# xnemo_r1-1.net
KiCad netlist of a schematic drawn in EAGLE
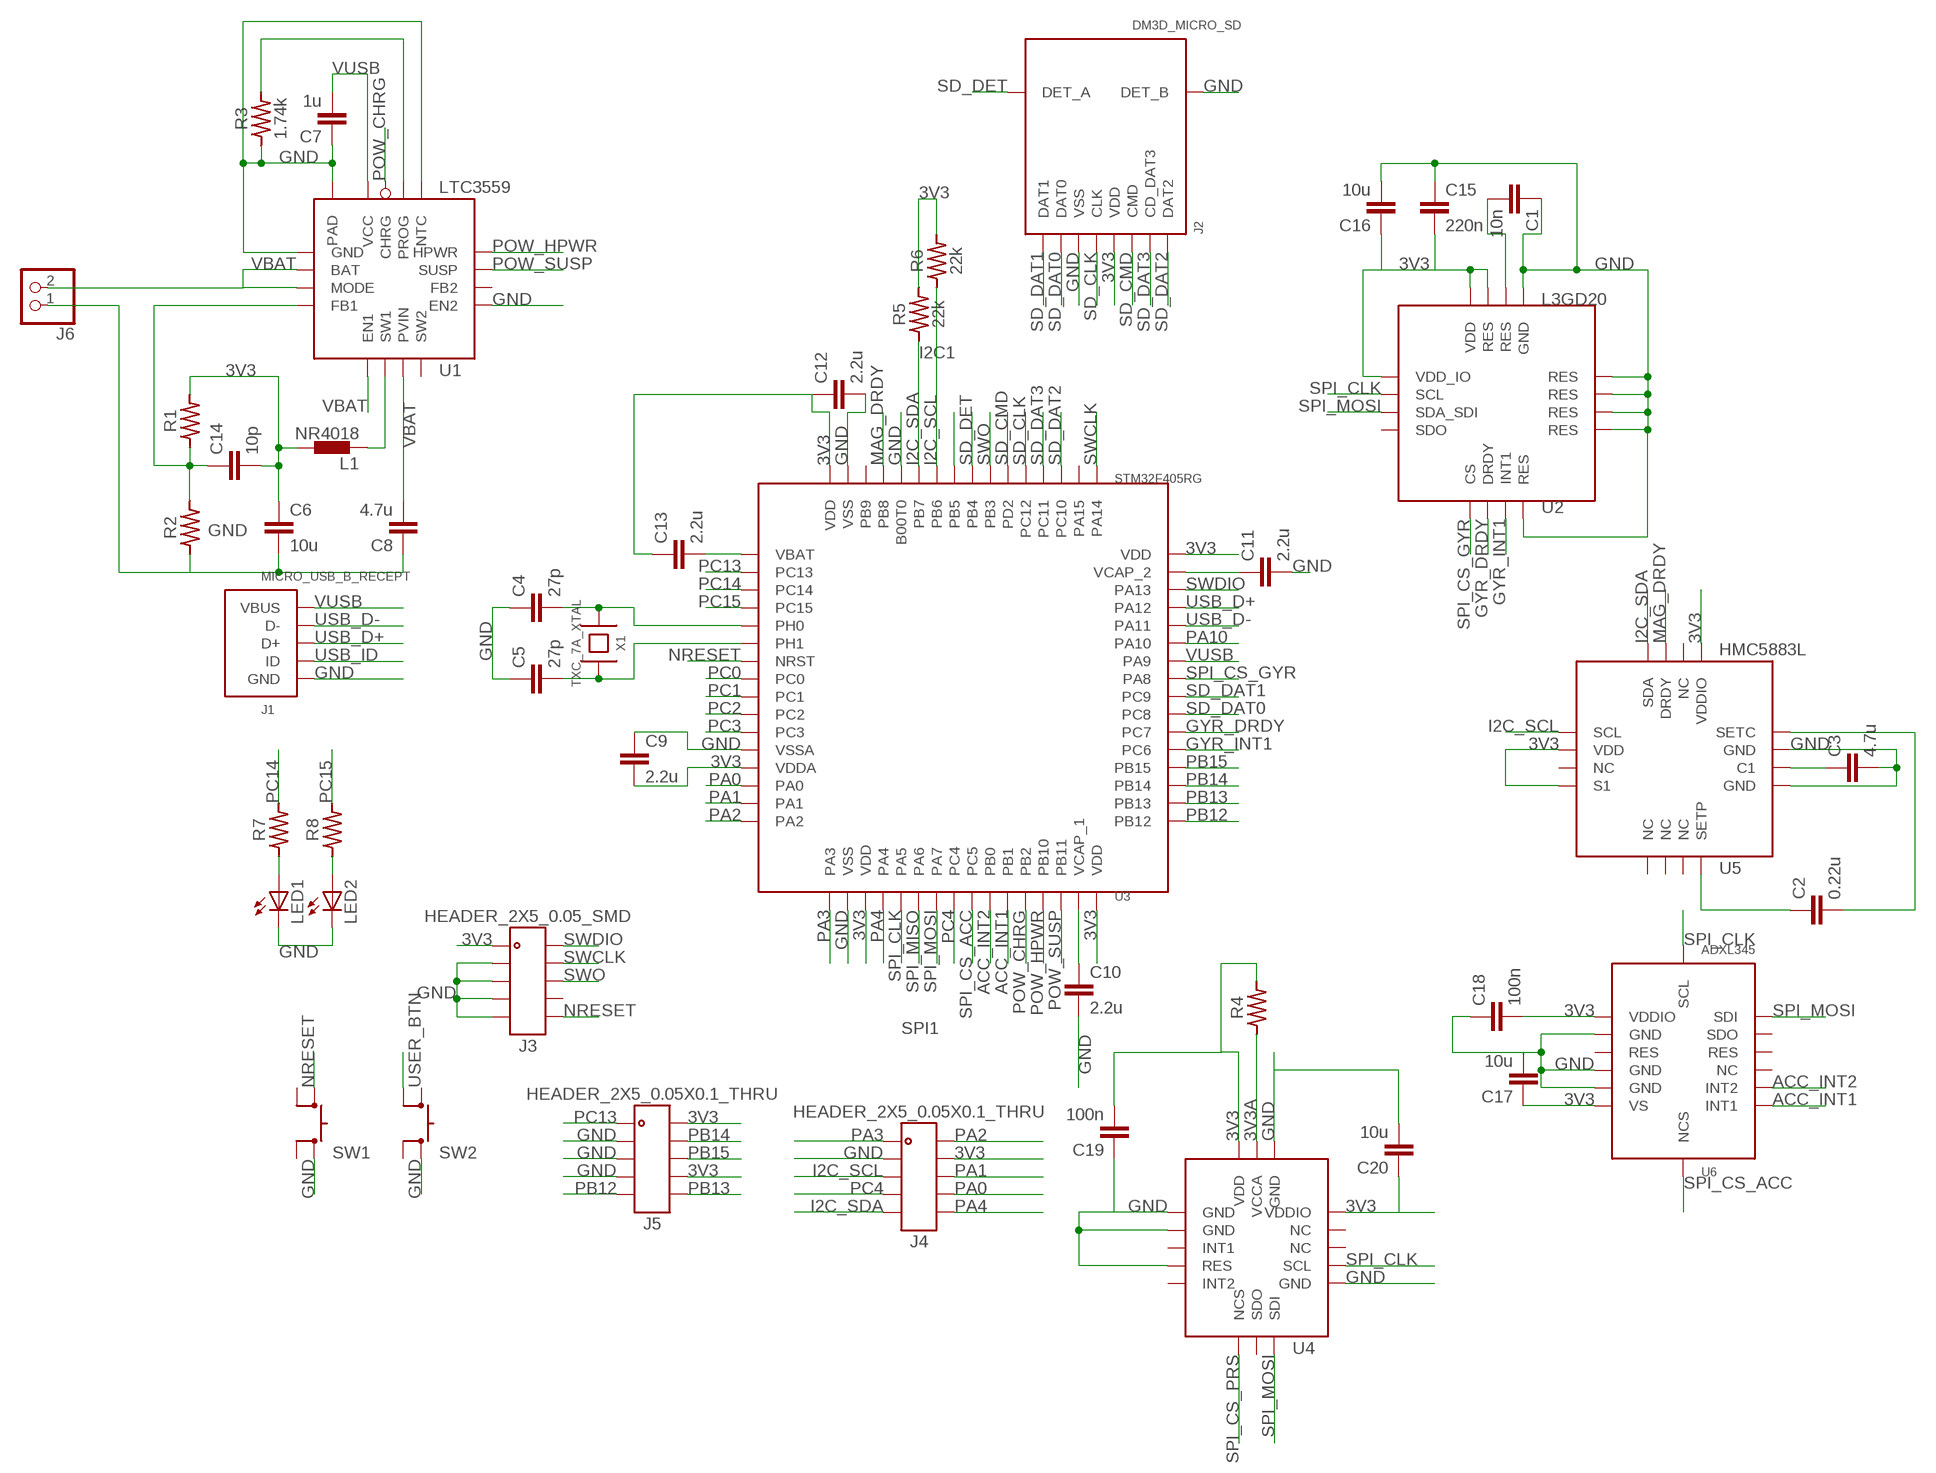
[diagram p0: schematic, sheet 1]

(export (version "E")
  (design (tool "Eeschema 10.0.6"))
  (components
    (comp (ref "C1")
      (value "10n")
      (footprint "eagle-import:C0402")
      (libsource (lib "eagle-import") (part "C-EUC0402"))
    )
    (comp (ref "C2")
      (value "0.22u")
      (footprint "eagle-import:C0402")
      (libsource (lib "eagle-import") (part "C-EUC0402"))
    )
    (comp (ref "C3")
      (value "4.7u")
      (footprint "eagle-import:C0805")
      (libsource (lib "eagle-import") (part "C-EUC0805"))
    )
    (comp (ref "C4")
      (value "27p")
      (footprint "eagle-import:C0402")
      (libsource (lib "eagle-import") (part "C-EUC0402"))
    )
    (comp (ref "C5")
      (value "27p")
      (footprint "eagle-import:C0402")
      (libsource (lib "eagle-import") (part "C-EUC0402"))
    )
    (comp (ref "C6")
      (value "10u")
      (footprint "eagle-import:C0805")
      (libsource (lib "eagle-import") (part "C-EUC0805"))
    )
    (comp (ref "C7")
      (value "1u")
      (footprint "eagle-import:C0603")
      (libsource (lib "eagle-import") (part "C-EUC0603"))
    )
    (comp (ref "C8")
      (value "4.7u")
      (footprint "eagle-import:C0805")
      (libsource (lib "eagle-import") (part "C-EUC0805"))
    )
    (comp (ref "C9")
      (value "2.2u")
      (footprint "eagle-import:C0603")
      (libsource (lib "eagle-import") (part "C-EUC0603"))
    )
    (comp (ref "C10")
      (value "2.2u")
      (footprint "eagle-import:C0603")
      (libsource (lib "eagle-import") (part "C-EUC0603"))
    )
    (comp (ref "C11")
      (value "2.2u")
      (footprint "eagle-import:C0603")
      (libsource (lib "eagle-import") (part "C-EUC0603"))
    )
    (comp (ref "C12")
      (value "2.2u")
      (footprint "eagle-import:C0603")
      (libsource (lib "eagle-import") (part "C-EUC0603"))
    )
    (comp (ref "C13")
      (value "2.2u")
      (footprint "eagle-import:C0603")
      (libsource (lib "eagle-import") (part "C-EUC0603"))
    )
    (comp (ref "C14")
      (value "10p")
      (footprint "eagle-import:C0402")
      (libsource (lib "eagle-import") (part "C-EUC0402"))
    )
    (comp (ref "C15")
      (value "220n")
      (footprint "eagle-import:C0402")
      (libsource (lib "eagle-import") (part "C-EUC0402"))
    )
    (comp (ref "C16")
      (value "10u")
      (footprint "eagle-import:C0805")
      (libsource (lib "eagle-import") (part "C-EUC0805"))
    )
    (comp (ref "C17")
      (value "10u")
      (footprint "eagle-import:C0805")
      (libsource (lib "eagle-import") (part "C-EUC0805"))
    )
    (comp (ref "C18")
      (value "100n")
      (footprint "eagle-import:C0402")
      (libsource (lib "eagle-import") (part "C-EUC0402"))
    )
    (comp (ref "C19")
      (value "100n")
      (footprint "eagle-import:C0402")
      (libsource (lib "eagle-import") (part "C-EUC0402"))
    )
    (comp (ref "C20")
      (value "10u")
      (footprint "eagle-import:C0805")
      (libsource (lib "eagle-import") (part "C-EUC0805"))
    )
    (comp (ref "J1")
      (value "MICRO_USB_B_RECEPT")
      (footprint "eagle-import:FCI_MICRO_USB_B")
      (libsource (lib "eagle-import") (part "MICRO_USB_B_RECEPT"))
    )
    (comp (ref "J2")
      (value "DM3D_MICRO_SD")
      (footprint "eagle-import:HIROSE_DM3D")
      (libsource (lib "eagle-import") (part "DM3D_MICRO_SD"))
    )
    (comp (ref "J3")
      (value "HEADER_2X5_0.05_SMD")
      (footprint "eagle-import:HEADER_2X5_0.05_SMD")
      (libsource (lib "eagle-import") (part "HEADER_2X5_0.05_SMD"))
    )
    (comp (ref "J4")
      (value "HEADER_2X5_0.05X0.1_THRU")
      (footprint "eagle-import:HEADER_2X5_0.05X0.1_THRU")
      (libsource (lib "eagle-import") (part "HEADER_2X5_0.05X0.1_THRU"))
    )
    (comp (ref "J5")
      (value "HEADER_2X5_0.05X0.1_THRU")
      (footprint "eagle-import:HEADER_2X5_0.05X0.1_THRU")
      (libsource (lib "eagle-import") (part "HEADER_2X5_0.05X0.1_THRU"))
    )
    (comp (ref "J6")
      (value "PINHD-1X2")
      (footprint "eagle-import:1X02")
      (libsource (lib "eagle-import") (part "PINHD-1X2"))
    )
    (comp (ref "L1")
      (value "NR4018")
      (footprint "eagle-import:L_401X")
      (libsource (lib "eagle-import") (part "NR4018"))
    )
    (comp (ref "LED1")
      (value "LEDCHIPLED_0603")
      (footprint "eagle-import:CHIPLED_0603")
      (libsource (lib "eagle-import") (part "LEDCHIPLED_0603"))
    )
    (comp (ref "LED2")
      (value "LEDCHIPLED_0603")
      (footprint "eagle-import:CHIPLED_0603")
      (libsource (lib "eagle-import") (part "LEDCHIPLED_0603"))
    )
    (comp (ref "R1")
      (value "RESISTOR-0402")
      (footprint "eagle-import:SMD0402")
      (libsource (lib "eagle-import") (part "RESISTOR-0402"))
    )
    (comp (ref "R2")
      (value "RESISTOR-0402")
      (footprint "eagle-import:SMD0402")
      (libsource (lib "eagle-import") (part "RESISTOR-0402"))
    )
    (comp (ref "R3")
      (value "1.74k")
      (footprint "eagle-import:SMD0402")
      (libsource (lib "eagle-import") (part "RESISTOR-0402"))
    )
    (comp (ref "R4")
      (value "RESISTOR-0603")
      (footprint "eagle-import:SMD0603")
      (libsource (lib "eagle-import") (part "RESISTOR-0603"))
    )
    (comp (ref "R5")
      (value "22k")
      (footprint "eagle-import:SMD0402")
      (libsource (lib "eagle-import") (part "RESISTOR-0402"))
    )
    (comp (ref "R6")
      (value "22k")
      (footprint "eagle-import:SMD0402")
      (libsource (lib "eagle-import") (part "RESISTOR-0402"))
    )
    (comp (ref "R7")
      (value "RESISTOR-0402")
      (footprint "eagle-import:SMD0402")
      (libsource (lib "eagle-import") (part "RESISTOR-0402"))
    )
    (comp (ref "R8")
      (value "RESISTOR-0402")
      (footprint "eagle-import:SMD0402")
      (libsource (lib "eagle-import") (part "RESISTOR-0402"))
    )
    (comp (ref "SW1")
      (value "ALPS_SKQG")
      (footprint "eagle-import:ALPS_SKQG")
      (libsource (lib "eagle-import") (part "ALPS_SKQG"))
    )
    (comp (ref "SW2")
      (value "ALPS_SKQG")
      (footprint "eagle-import:ALPS_SKQG")
      (libsource (lib "eagle-import") (part "ALPS_SKQG"))
    )
    (comp (ref "U1")
      (value "LTC3559")
      (footprint "eagle-import:LT_QFN16_3X3")
      (libsource (lib "eagle-import") (part "LTC3559"))
    )
    (comp (ref "U2")
      (value "L3GD20")
      (footprint "eagle-import:ST_LGA16_4X4")
      (libsource (lib "eagle-import") (part "L3GD20"))
    )
    (comp (ref "U3")
      (value "STM32F405RG")
      (footprint "eagle-import:ST_LQFP64")
      (libsource (lib "eagle-import") (part "STM32F405RG"))
    )
    (comp (ref "U4")
      (value "LPS331AP")
      (footprint "eagle-import:ST_HCLGA-16L")
      (libsource (lib "eagle-import") (part "LPS331AP"))
    )
    (comp (ref "U5")
      (value "HMC5883L")
      (footprint "eagle-import:HW_LCC16_3X3")
      (libsource (lib "eagle-import") (part "HMC5883L"))
    )
    (comp (ref "U6")
      (value "ADXL345")
      (footprint "eagle-import:AD_LGA14_3X5")
      (libsource (lib "eagle-import") (part "ADXL345"))
    )
    (comp (ref "X1")
      (value "TXC_7A_XTAL")
      (footprint "eagle-import:TXC_7A_XTAL")
      (libsource (lib "eagle-import") (part "TXC_7A_XTAL"))
    )
  )
  (nets
    (net (code "1") (name "/3V3") (class "Default")
      (node (ref "C12") (pin "1") (pinfunction "1_1") (pintype "passive"))
      (node (ref "C13") (pin "1") (pinfunction "1_1") (pintype "passive"))
      (node (ref "C14") (pin "2") (pinfunction "2_2") (pintype "passive"))
      (node (ref "C15") (pin "2") (pinfunction "2_2") (pintype "passive"))
      (node (ref "C16") (pin "1") (pinfunction "1_1") (pintype "passive"))
      (node (ref "C17") (pin "1") (pinfunction "1_1") (pintype "passive"))
      (node (ref "C18") (pin "2") (pinfunction "2_2") (pintype "passive"))
      (node (ref "C19") (pin "2") (pinfunction "2_2") (pintype "passive"))
      (node (ref "C20") (pin "1") (pinfunction "1_1") (pintype "passive"))
      (node (ref "C6") (pin "1") (pinfunction "1_1") (pintype "passive"))
      (node (ref "C9") (pin "2") (pinfunction "2_2") (pintype "passive"))
      (node (ref "J2") (pin "P$5") (pinfunction "VDD_P$5") (pintype "bidirectional"))
      (node (ref "J3") (pin "1") (pinfunction "1_1") (pintype "bidirectional"))
      (node (ref "J4") (pin "4") (pinfunction "4_4") (pintype "bidirectional"))
      (node (ref "J5") (pin "2") (pinfunction "2_2") (pintype "bidirectional"))
      (node (ref "J5") (pin "8") (pinfunction "8_8") (pintype "bidirectional"))
      (node (ref "L1") (pin "P$2") (pinfunction "2_P$2") (pintype "passive"))
      (node (ref "R1") (pin "P$1") (pinfunction "P$1_P$1") (pintype "passive"))
      (node (ref "R4") (pin "P$1") (pinfunction "P$1_P$1") (pintype "passive"))
      (node (ref "R5") (pin "P$1") (pinfunction "P$1_P$1") (pintype "passive"))
      (node (ref "R6") (pin "P$1") (pinfunction "P$1_P$1") (pintype "passive"))
      (node (ref "U2") (pin "P$1") (pinfunction "VDD_IO_P$1") (pintype "bidirectional"))
      (node (ref "U2") (pin "P$15") (pinfunction "RES_P$15") (pintype "bidirectional"))
      (node (ref "U2") (pin "P$16") (pinfunction "VDD_P$16") (pintype "bidirectional"))
      (node (ref "U3") (pin "P$13") (pinfunction "VDDA_P$13") (pintype "bidirectional"))
      (node (ref "U3") (pin "P$19") (pinfunction "VDD_P$19") (pintype "bidirectional"))
      (node (ref "U3") (pin "P$32") (pinfunction "VDD_P$32") (pintype "bidirectional"))
      (node (ref "U3") (pin "P$48") (pinfunction "VDD_P$48") (pintype "bidirectional"))
      (node (ref "U3") (pin "P$64") (pinfunction "VDD_P$64") (pintype "bidirectional"))
      (node (ref "U4") (pin "P$1") (pinfunction "VDDIO_P$1") (pintype "bidirectional"))
      (node (ref "U4") (pin "P$14") (pinfunction "VDD_P$14") (pintype "bidirectional"))
      (node (ref "U5") (pin "P$13") (pinfunction "VDDIO_P$13") (pintype "bidirectional"))
      (node (ref "U5") (pin "P$2") (pinfunction "VDD_P$2") (pintype "bidirectional"))
      (node (ref "U5") (pin "P$4") (pinfunction "S1_P$4") (pintype "bidirectional"))
      (node (ref "U6") (pin "P$1") (pinfunction "VDDIO_P$1") (pintype "bidirectional"))
      (node (ref "U6") (pin "P$6") (pinfunction "VS_P$6") (pintype "bidirectional"))
    )
    (net (code "2") (name "/3V3A") (class "Default")
      (node (ref "R4") (pin "P$2") (pinfunction "P$2_P$2") (pintype "passive"))
      (node (ref "U4") (pin "P$15") (pinfunction "VCCA_P$15") (pintype "bidirectional"))
    )
    (net (code "3") (name "/ACC_INT1") (class "Default")
      (node (ref "U3") (pin "P$27") (pinfunction "PB1_P$27") (pintype "bidirectional"))
      (node (ref "U6") (pin "P$8") (pinfunction "INT1_P$8") (pintype "bidirectional"))
    )
    (net (code "4") (name "/ACC_INT2") (class "Default")
      (node (ref "U3") (pin "P$26") (pinfunction "PB0_P$26") (pintype "bidirectional"))
      (node (ref "U6") (pin "P$9") (pinfunction "INT2_P$9") (pintype "bidirectional"))
    )
    (net (code "5") (name "/GND") (class "Default")
      (node (ref "C1") (pin "1") (pinfunction "1_1") (pintype "passive"))
      (node (ref "C10") (pin "2") (pinfunction "2_2") (pintype "passive"))
      (node (ref "C11") (pin "2") (pinfunction "2_2") (pintype "passive"))
      (node (ref "C12") (pin "2") (pinfunction "2_2") (pintype "passive"))
      (node (ref "C15") (pin "1") (pinfunction "1_1") (pintype "passive"))
      (node (ref "C16") (pin "2") (pinfunction "2_2") (pintype "passive"))
      (node (ref "C17") (pin "2") (pinfunction "2_2") (pintype "passive"))
      (node (ref "C18") (pin "1") (pinfunction "1_1") (pintype "passive"))
      (node (ref "C19") (pin "1") (pinfunction "1_1") (pintype "passive"))
      (node (ref "C20") (pin "2") (pinfunction "2_2") (pintype "passive"))
      (node (ref "C3") (pin "2") (pinfunction "2_2") (pintype "passive"))
      (node (ref "C4") (pin "1") (pinfunction "1_1") (pintype "passive"))
      (node (ref "C5") (pin "1") (pinfunction "1_1") (pintype "passive"))
      (node (ref "C6") (pin "2") (pinfunction "2_2") (pintype "passive"))
      (node (ref "C7") (pin "1") (pinfunction "1_1") (pintype "passive"))
      (node (ref "C8") (pin "1") (pinfunction "1_1") (pintype "passive"))
      (node (ref "C9") (pin "1") (pinfunction "1_1") (pintype "passive"))
      (node (ref "J1") (pin "P$5") (pinfunction "GND_P$5") (pintype "bidirectional"))
      (node (ref "J2") (pin "P$3") (pinfunction "VSS_P$3") (pintype "bidirectional"))
      (node (ref "J2") (pin "P$9") (pinfunction "DET_B_P$9") (pintype "bidirectional"))
      (node (ref "J3") (pin "3") (pinfunction "3_3") (pintype "bidirectional"))
      (node (ref "J3") (pin "5") (pinfunction "5_5") (pintype "bidirectional"))
      (node (ref "J3") (pin "7") (pinfunction "7_7") (pintype "bidirectional"))
      (node (ref "J3") (pin "9") (pinfunction "9_9") (pintype "bidirectional"))
      (node (ref "J4") (pin "3") (pinfunction "3_3") (pintype "bidirectional"))
      (node (ref "J5") (pin "3") (pinfunction "3_3") (pintype "bidirectional"))
      (node (ref "J5") (pin "5") (pinfunction "5_5") (pintype "bidirectional"))
      (node (ref "J5") (pin "7") (pinfunction "7_7") (pintype "bidirectional"))
      (node (ref "J6") (pin "1") (pinfunction "1_1") (pintype "passive"))
      (node (ref "LED1") (pin "C") (pinfunction "C_C") (pintype "passive"))
      (node (ref "LED2") (pin "C") (pinfunction "C_C") (pintype "passive"))
      (node (ref "R2") (pin "P$2") (pinfunction "P$2_P$2") (pintype "passive"))
      (node (ref "R3") (pin "P$2") (pinfunction "P$2_P$2") (pintype "passive"))
      (node (ref "SW1") (pin "2_2") (pinfunction "2_2_2") (pintype "bidirectional"))
      (node (ref "SW2") (pin "2_2") (pinfunction "2_2_2") (pintype "bidirectional"))
      (node (ref "U1") (pin "P$1") (pinfunction "GND_P$1") (pintype "bidirectional"))
      (node (ref "U1") (pin "P$13") (pinfunction "NTC_P$13") (pintype "bidirectional"))
      (node (ref "U1") (pin "P$17") (pinfunction "PAD_P$17") (pintype "bidirectional"))
      (node (ref "U1") (pin "P$9") (pinfunction "EN2_P$9") (pintype "bidirectional"))
      (node (ref "U2") (pin "P$10") (pinfunction "RES_P$10") (pintype "bidirectional"))
      (node (ref "U2") (pin "P$11") (pinfunction "RES_P$11") (pintype "bidirectional"))
      (node (ref "U2") (pin "P$12") (pinfunction "RES_P$12") (pintype "bidirectional"))
      (node (ref "U2") (pin "P$13") (pinfunction "GND_P$13") (pintype "bidirectional"))
      (node (ref "U2") (pin "P$8") (pinfunction "RES_P$8") (pintype "bidirectional"))
      (node (ref "U2") (pin "P$9") (pinfunction "RES_P$9") (pintype "bidirectional"))
      (node (ref "U3") (pin "P$12") (pinfunction "VSSA_P$12") (pintype "bidirectional"))
      (node (ref "U3") (pin "P$18") (pinfunction "VSS_P$18") (pintype "bidirectional"))
      (node (ref "U3") (pin "P$60") (pinfunction "B00T0_P$60") (pintype "bidirectional"))
      (node (ref "U3") (pin "P$63") (pinfunction "VSS_P$63") (pintype "bidirectional"))
      (node (ref "U4") (pin "P$10") (pinfunction "RES_P$10") (pintype "bidirectional"))
      (node (ref "U4") (pin "P$12") (pinfunction "GND_P$12") (pintype "bidirectional"))
      (node (ref "U4") (pin "P$13") (pinfunction "GND_P$13") (pintype "bidirectional"))
      (node (ref "U4") (pin "P$16") (pinfunction "GND_P$16") (pintype "bidirectional"))
      (node (ref "U4") (pin "P$5") (pinfunction "GND_P$5") (pintype "bidirectional"))
      (node (ref "U5") (pin "P$11") (pinfunction "GND_P$11") (pintype "bidirectional"))
      (node (ref "U5") (pin "P$9") (pinfunction "GND_P$9") (pintype "bidirectional"))
      (node (ref "U6") (pin "P$2") (pinfunction "GND_P$2") (pintype "bidirectional"))
      (node (ref "U6") (pin "P$4") (pinfunction "GND_P$4") (pintype "bidirectional"))
      (node (ref "U6") (pin "P$5") (pinfunction "GND_P$5") (pintype "bidirectional"))
    )
    (net (code "6") (name "/GYR_DRDY") (class "Default")
      (node (ref "U2") (pin "P$6") (pinfunction "DRDY_P$6") (pintype "bidirectional"))
      (node (ref "U3") (pin "P$38") (pinfunction "PC7_P$38") (pintype "bidirectional"))
    )
    (net (code "7") (name "/GYR_INT1") (class "Default")
      (node (ref "U2") (pin "P$7") (pinfunction "INT1_P$7") (pintype "bidirectional"))
      (node (ref "U3") (pin "P$37") (pinfunction "PC6_P$37") (pintype "bidirectional"))
    )
    (net (code "8") (name "/I2C_SCL") (class "Default")
      (node (ref "J4") (pin "5") (pinfunction "5_5") (pintype "bidirectional"))
      (node (ref "R6") (pin "P$2") (pinfunction "P$2_P$2") (pintype "passive"))
      (node (ref "U3") (pin "P$58") (pinfunction "PB6_P$58") (pintype "bidirectional"))
      (node (ref "U5") (pin "P$1") (pinfunction "SCL_P$1") (pintype "bidirectional"))
    )
    (net (code "9") (name "/I2C_SDA") (class "Default")
      (node (ref "J4") (pin "9") (pinfunction "9_9") (pintype "bidirectional"))
      (node (ref "R5") (pin "P$2") (pinfunction "P$2_P$2") (pintype "passive"))
      (node (ref "U3") (pin "P$59") (pinfunction "PB7_P$59") (pintype "bidirectional"))
      (node (ref "U5") (pin "P$16") (pinfunction "SDA_P$16") (pintype "bidirectional"))
    )
    (net (code "10") (name "/MAG_DRDY") (class "Default")
      (node (ref "U3") (pin "P$61") (pinfunction "PB8_P$61") (pintype "bidirectional"))
      (node (ref "U5") (pin "P$15") (pinfunction "DRDY_P$15") (pintype "bidirectional"))
    )
    (net (code "11") (name "/NRESET") (class "Default")
      (node (ref "J3") (pin "10") (pinfunction "10_10") (pintype "bidirectional"))
      (node (ref "SW1") (pin "1_2") (pinfunction "1_1_2") (pintype "bidirectional"))
      (node (ref "U3") (pin "P$7") (pinfunction "NRST_P$7") (pintype "bidirectional"))
    )
    (net (code "12") (name "/PA0") (class "Default")
      (node (ref "J4") (pin "8") (pinfunction "8_8") (pintype "bidirectional"))
      (node (ref "U3") (pin "P$14") (pinfunction "PA0_P$14") (pintype "bidirectional"))
    )
    (net (code "13") (name "/PA1") (class "Default")
      (node (ref "J4") (pin "6") (pinfunction "6_6") (pintype "bidirectional"))
      (node (ref "U3") (pin "P$15") (pinfunction "PA1_P$15") (pintype "bidirectional"))
    )
    (net (code "14") (name "/PA2") (class "Default")
      (node (ref "J4") (pin "2") (pinfunction "2_2") (pintype "bidirectional"))
      (node (ref "U3") (pin "P$16") (pinfunction "PA2_P$16") (pintype "bidirectional"))
    )
    (net (code "15") (name "/PA3") (class "Default")
      (node (ref "J4") (pin "1") (pinfunction "1_1") (pintype "bidirectional"))
      (node (ref "U3") (pin "P$17") (pinfunction "PA3_P$17") (pintype "bidirectional"))
    )
    (net (code "16") (name "/PA4") (class "Default")
      (node (ref "J4") (pin "10") (pinfunction "10_10") (pintype "bidirectional"))
      (node (ref "U3") (pin "P$20") (pinfunction "PA4_P$20") (pintype "bidirectional"))
    )
    (net (code "17") (name "/PA10") (class "Default")
      (node (ref "U3") (pin "P$43") (pinfunction "PA10_P$43") (pintype "bidirectional"))
    )
    (net (code "18") (name "/PB12") (class "Default")
      (node (ref "J5") (pin "9") (pinfunction "9_9") (pintype "bidirectional"))
      (node (ref "U3") (pin "P$33") (pinfunction "PB12_P$33") (pintype "bidirectional"))
    )
    (net (code "19") (name "/PB13") (class "Default")
      (node (ref "J5") (pin "10") (pinfunction "10_10") (pintype "bidirectional"))
      (node (ref "U3") (pin "P$34") (pinfunction "PB13_P$34") (pintype "bidirectional"))
    )
    (net (code "20") (name "/PB14") (class "Default")
      (node (ref "J5") (pin "4") (pinfunction "4_4") (pintype "bidirectional"))
      (node (ref "U3") (pin "P$35") (pinfunction "PB14_P$35") (pintype "bidirectional"))
    )
    (net (code "21") (name "/PB15") (class "Default")
      (node (ref "J5") (pin "6") (pinfunction "6_6") (pintype "bidirectional"))
      (node (ref "U3") (pin "P$36") (pinfunction "PB15_P$36") (pintype "bidirectional"))
    )
    (net (code "22") (name "/PC0") (class "Default")
      (node (ref "U3") (pin "P$8") (pinfunction "PC0_P$8") (pintype "bidirectional"))
    )
    (net (code "23") (name "/PC1") (class "Default")
      (node (ref "U3") (pin "P$9") (pinfunction "PC1_P$9") (pintype "bidirectional"))
    )
    (net (code "24") (name "/PC2") (class "Default")
      (node (ref "U3") (pin "P$10") (pinfunction "PC2_P$10") (pintype "bidirectional"))
    )
    (net (code "25") (name "/PC3") (class "Default")
      (node (ref "U3") (pin "P$11") (pinfunction "PC3_P$11") (pintype "bidirectional"))
    )
    (net (code "26") (name "/PC4") (class "Default")
      (node (ref "J4") (pin "7") (pinfunction "7_7") (pintype "bidirectional"))
      (node (ref "U3") (pin "P$24") (pinfunction "PC4_P$24") (pintype "bidirectional"))
    )
    (net (code "27") (name "/PC13") (class "Default")
      (node (ref "J5") (pin "1") (pinfunction "1_1") (pintype "bidirectional"))
      (node (ref "U3") (pin "P$2") (pinfunction "PC13_P$2") (pintype "bidirectional"))
    )
    (net (code "28") (name "/PC14") (class "Default")
      (node (ref "R7") (pin "P$1") (pinfunction "P$1_P$1") (pintype "passive"))
      (node (ref "U3") (pin "P$3") (pinfunction "PC14_P$3") (pintype "bidirectional"))
    )
    (net (code "29") (name "/PC15") (class "Default")
      (node (ref "R8") (pin "P$1") (pinfunction "P$1_P$1") (pintype "passive"))
      (node (ref "U3") (pin "P$4") (pinfunction "PC15_P$4") (pintype "bidirectional"))
    )
    (net (code "30") (name "/POW_CHRG") (class "Default")
      (node (ref "U1") (pin "P$15") (pinfunction "CHRG_P$15") (pintype "bidirectional"))
      (node (ref "U3") (pin "P$28") (pinfunction "PB2_P$28") (pintype "bidirectional"))
    )
    (net (code "31") (name "/POW_HPWR") (class "Default")
      (node (ref "U1") (pin "P$12") (pinfunction "HPWR_P$12") (pintype "bidirectional"))
      (node (ref "U3") (pin "P$29") (pinfunction "PB10_P$29") (pintype "bidirectional"))
    )
    (net (code "32") (name "/POW_SUSP") (class "Default")
      (node (ref "U1") (pin "P$11") (pinfunction "SUSP_P$11") (pintype "bidirectional"))
      (node (ref "U3") (pin "P$30") (pinfunction "PB11_P$30") (pintype "bidirectional"))
    )
    (net (code "33") (name "/SD_CLK") (class "Default")
      (node (ref "J2") (pin "P$4") (pinfunction "CLK_P$4") (pintype "bidirectional"))
      (node (ref "U3") (pin "P$53") (pinfunction "PC12_P$53") (pintype "bidirectional"))
    )
    (net (code "34") (name "/SD_CMD") (class "Default")
      (node (ref "J2") (pin "P$6") (pinfunction "CMD_P$6") (pintype "bidirectional"))
      (node (ref "U3") (pin "P$54") (pinfunction "PD2_P$54") (pintype "bidirectional"))
    )
    (net (code "35") (name "/SD_DAT0") (class "Default")
      (node (ref "J2") (pin "P$2") (pinfunction "DAT0_P$2") (pintype "bidirectional"))
      (node (ref "U3") (pin "P$39") (pinfunction "PC8_P$39") (pintype "bidirectional"))
    )
    (net (code "36") (name "/SD_DAT1") (class "Default")
      (node (ref "J2") (pin "P$1") (pinfunction "DAT1_P$1") (pintype "bidirectional"))
      (node (ref "U3") (pin "P$40") (pinfunction "PC9_P$40") (pintype "bidirectional"))
    )
    (net (code "37") (name "/SD_DAT2") (class "Default")
      (node (ref "J2") (pin "P$8") (pinfunction "DAT2_P$8") (pintype "bidirectional"))
      (node (ref "U3") (pin "P$51") (pinfunction "PC10_P$51") (pintype "bidirectional"))
    )
    (net (code "38") (name "/SD_DAT3") (class "Default")
      (node (ref "J2") (pin "P$7") (pinfunction "CD_DAT3_P$7") (pintype "bidirectional"))
      (node (ref "U3") (pin "P$52") (pinfunction "PC11_P$52") (pintype "bidirectional"))
    )
    (net (code "39") (name "/SD_DET") (class "Default")
      (node (ref "J2") (pin "P$10") (pinfunction "DET_A_P$10") (pintype "bidirectional"))
      (node (ref "U3") (pin "P$56") (pinfunction "PB4_P$56") (pintype "bidirectional"))
    )
    (net (code "40") (name "/SPI_CLK") (class "Default")
      (node (ref "U2") (pin "P$2") (pinfunction "SCL_P$2") (pintype "bidirectional"))
      (node (ref "U3") (pin "P$21") (pinfunction "PA5_P$21") (pintype "bidirectional"))
      (node (ref "U4") (pin "P$4") (pinfunction "SCL_P$4") (pintype "bidirectional"))
      (node (ref "U6") (pin "P$14") (pinfunction "SCL_P$14") (pintype "bidirectional"))
    )
    (net (code "41") (name "/SPI_CS_ACC") (class "Default")
      (node (ref "U3") (pin "P$25") (pinfunction "PC5_P$25") (pintype "bidirectional"))
      (node (ref "U6") (pin "P$7") (pinfunction "NCS_P$7") (pintype "bidirectional"))
    )
    (net (code "42") (name "/SPI_CS_GYR") (class "Default")
      (node (ref "U2") (pin "P$5") (pinfunction "CS_P$5") (pintype "bidirectional"))
      (node (ref "U3") (pin "P$41") (pinfunction "PA8_P$41") (pintype "bidirectional"))
    )
    (net (code "43") (name "/SPI_CS_PRS") (class "Default")
      (node (ref "U4") (pin "P$8") (pinfunction "NCS_P$8") (pintype "bidirectional"))
    )
    (net (code "44") (name "/SPI_MISO") (class "Default")
      (node (ref "U3") (pin "P$22") (pinfunction "PA6_P$22") (pintype "bidirectional"))
    )
    (net (code "45") (name "/SPI_MOSI") (class "Default")
      (node (ref "U2") (pin "P$3") (pinfunction "SDA_SDI_P$3") (pintype "bidirectional"))
      (node (ref "U3") (pin "P$23") (pinfunction "PA7_P$23") (pintype "bidirectional"))
      (node (ref "U4") (pin "P$6") (pinfunction "SDI_P$6") (pintype "bidirectional"))
      (node (ref "U6") (pin "P$13") (pinfunction "SDI_P$13") (pintype "bidirectional"))
    )
    (net (code "46") (name "/SWCLK") (class "Default")
      (node (ref "J3") (pin "4") (pinfunction "4_4") (pintype "bidirectional"))
      (node (ref "U3") (pin "P$49") (pinfunction "PA14_P$49") (pintype "bidirectional"))
    )
    (net (code "47") (name "/SWDIO") (class "Default")
      (node (ref "J3") (pin "2") (pinfunction "2_2") (pintype "bidirectional"))
      (node (ref "U3") (pin "P$46") (pinfunction "PA13_P$46") (pintype "bidirectional"))
    )
    (net (code "48") (name "/SWO") (class "Default")
      (node (ref "J3") (pin "6") (pinfunction "6_6") (pintype "bidirectional"))
      (node (ref "U3") (pin "P$55") (pinfunction "PB3_P$55") (pintype "bidirectional"))
    )
    (net (code "49") (name "/USB_D+") (class "Default")
      (node (ref "J1") (pin "P$3") (pinfunction "D+_P$3") (pintype "bidirectional"))
      (node (ref "U3") (pin "P$45") (pinfunction "PA12_P$45") (pintype "bidirectional"))
    )
    (net (code "50") (name "/USB_D-") (class "Default")
      (node (ref "J1") (pin "P$2") (pinfunction "D-_P$2") (pintype "bidirectional"))
      (node (ref "U3") (pin "P$44") (pinfunction "PA11_P$44") (pintype "bidirectional"))
    )
    (net (code "51") (name "/USB_ID") (class "Default")
      (node (ref "J1") (pin "P$4") (pinfunction "ID_P$4") (pintype "bidirectional"))
    )
    (net (code "52") (name "/USER_BTN") (class "Default")
      (node (ref "SW2") (pin "1_1") (pinfunction "1_1_1") (pintype "bidirectional"))
      (node (ref "U3") (pin "P$57") (pinfunction "PB5_P$57") (pintype "bidirectional"))
    )
    (net (code "53") (name "/VBAT") (class "Default")
      (node (ref "C8") (pin "2") (pinfunction "2_2") (pintype "passive"))
      (node (ref "J6") (pin "2") (pinfunction "2_2") (pintype "passive"))
      (node (ref "U1") (pin "P$2") (pinfunction "BAT_P$2") (pintype "bidirectional"))
      (node (ref "U1") (pin "P$3") (pinfunction "MODE_P$3") (pintype "bidirectional"))
      (node (ref "U1") (pin "P$5") (pinfunction "EN1_P$5") (pintype "bidirectional"))
      (node (ref "U1") (pin "P$7") (pinfunction "PVIN_P$7") (pintype "bidirectional"))
    )
    (net (code "54") (name "/VUSB") (class "Default")
      (node (ref "C7") (pin "2") (pinfunction "2_2") (pintype "passive"))
      (node (ref "J1") (pin "P$1") (pinfunction "VBUS_P$1") (pintype "bidirectional"))
      (node (ref "U1") (pin "P$16") (pinfunction "VCC_P$16") (pintype "bidirectional"))
      (node (ref "U3") (pin "P$42") (pinfunction "PA9_P$42") (pintype "bidirectional"))
    )
    (net (code "55") (name "Net-(C1-Pad2)") (class "Default")
      (node (ref "C1") (pin "2") (pinfunction "2_2") (pintype "passive"))
      (node (ref "U2") (pin "P$14") (pinfunction "RES_P$14") (pintype "bidirectional"))
    )
    (net (code "56") (name "Net-(L1-1)") (class "Default")
      (node (ref "L1") (pin "P$1") (pinfunction "1_P$1") (pintype "passive"))
      (node (ref "U1") (pin "P$6") (pinfunction "SW1_P$6") (pintype "bidirectional"))
    )
    (net (code "57") (name "Net-(LED1-PadA)") (class "Default")
      (node (ref "LED1") (pin "A") (pinfunction "A_A") (pintype "passive"))
      (node (ref "R7") (pin "P$2") (pinfunction "P$2_P$2") (pintype "passive"))
    )
    (net (code "58") (name "Net-(LED2-PadA)") (class "Default")
      (node (ref "LED2") (pin "A") (pinfunction "A_A") (pintype "passive"))
      (node (ref "R8") (pin "P$2") (pinfunction "P$2_P$2") (pintype "passive"))
    )
    (net (code "59") (name "Net-(U1-FB1)") (class "Default")
      (node (ref "C14") (pin "1") (pinfunction "1_1") (pintype "passive"))
      (node (ref "R1") (pin "P$2") (pinfunction "P$2_P$2") (pintype "passive"))
      (node (ref "R2") (pin "P$1") (pinfunction "P$1_P$1") (pintype "passive"))
      (node (ref "U1") (pin "P$4") (pinfunction "FB1_P$4") (pintype "bidirectional"))
    )
    (net (code "60") (name "Net-(U1-PROG)") (class "Default")
      (node (ref "R3") (pin "P$1") (pinfunction "P$1_P$1") (pintype "passive"))
      (node (ref "U1") (pin "P$14") (pinfunction "PROG_P$14") (pintype "bidirectional"))
    )
    (net (code "61") (name "Net-(U3-PH0)") (class "Default")
      (node (ref "C4") (pin "2") (pinfunction "2_2") (pintype "passive"))
      (node (ref "U3") (pin "P$5") (pinfunction "PH0_P$5") (pintype "bidirectional"))
      (node (ref "X1") (pin "P$2") (pinfunction "P$2_P$2") (pintype "bidirectional"))
    )
    (net (code "62") (name "Net-(U3-PH1)") (class "Default")
      (node (ref "C5") (pin "2") (pinfunction "2_2") (pintype "passive"))
      (node (ref "U3") (pin "P$6") (pinfunction "PH1_P$6") (pintype "bidirectional"))
      (node (ref "X1") (pin "P$1") (pinfunction "P$1_P$1") (pintype "bidirectional"))
    )
    (net (code "63") (name "Net-(U3-VBAT)") (class "Default")
      (node (ref "C13") (pin "2") (pinfunction "2_2") (pintype "passive"))
      (node (ref "U3") (pin "P$1") (pinfunction "VBAT_P$1") (pintype "bidirectional"))
    )
    (net (code "64") (name "Net-(U3-VCAP_1)") (class "Default")
      (node (ref "C10") (pin "1") (pinfunction "1_1") (pintype "passive"))
      (node (ref "U3") (pin "P$31") (pinfunction "VCAP_1_P$31") (pintype "bidirectional"))
    )
    (net (code "65") (name "Net-(U3-VCAP_2)") (class "Default")
      (node (ref "C11") (pin "1") (pinfunction "1_1") (pintype "passive"))
      (node (ref "U3") (pin "P$47") (pinfunction "VCAP_2_P$47") (pintype "bidirectional"))
    )
    (net (code "66") (name "Net-(U5-C1)") (class "Default")
      (node (ref "C3") (pin "1") (pinfunction "1_1") (pintype "passive"))
      (node (ref "U5") (pin "P$10") (pinfunction "C1_P$10") (pintype "bidirectional"))
    )
    (net (code "67") (name "Net-(U5-SETC)") (class "Default")
      (node (ref "C2") (pin "2") (pinfunction "2_2") (pintype "passive"))
      (node (ref "U5") (pin "P$12") (pinfunction "SETC_P$12") (pintype "bidirectional"))
    )
    (net (code "68") (name "Net-(U5-SETP)") (class "Default")
      (node (ref "C2") (pin "1") (pinfunction "1_1") (pintype "passive"))
      (node (ref "U5") (pin "P$8") (pinfunction "SETP_P$8") (pintype "bidirectional"))
    )
    (net (code "69") (name "unconnected-(J3-Pad8)") (class "Default")
      (node (ref "J3") (pin "8") (pinfunction "8_8") (pintype "bidirectional"))
    )
    (net (code "70") (name "unconnected-(SW1-1-Pad1_1)") (class "Default")
      (node (ref "SW1") (pin "1_1") (pinfunction "1_1_1") (pintype "bidirectional"))
    )
    (net (code "71") (name "unconnected-(SW1-2-Pad2_1)") (class "Default")
      (node (ref "SW1") (pin "2_1") (pinfunction "2_2_1") (pintype "bidirectional"))
    )
    (net (code "72") (name "unconnected-(SW2-1-Pad1_2)") (class "Default")
      (node (ref "SW2") (pin "1_2") (pinfunction "1_1_2") (pintype "bidirectional"))
    )
    (net (code "73") (name "unconnected-(SW2-2-Pad2_1)") (class "Default")
      (node (ref "SW2") (pin "2_1") (pinfunction "2_2_1") (pintype "bidirectional"))
    )
    (net (code "74") (name "unconnected-(U1-FB2-PadP$10)") (class "Default")
      (node (ref "U1") (pin "P$10") (pinfunction "FB2_P$10") (pintype "bidirectional"))
    )
    (net (code "75") (name "unconnected-(U1-SW2-PadP$8)") (class "Default")
      (node (ref "U1") (pin "P$8") (pinfunction "SW2_P$8") (pintype "bidirectional"))
    )
    (net (code "76") (name "unconnected-(U2-SDO-PadP$4)") (class "Default")
      (node (ref "U2") (pin "P$4") (pinfunction "SDO_P$4") (pintype "bidirectional"))
    )
    (net (code "77") (name "unconnected-(U3-PA15-PadP$50)") (class "Default")
      (node (ref "U3") (pin "P$50") (pinfunction "PA15_P$50") (pintype "bidirectional"))
    )
    (net (code "78") (name "unconnected-(U3-PB9-PadP$62)") (class "Default")
      (node (ref "U3") (pin "P$62") (pinfunction "PB9_P$62") (pintype "bidirectional"))
    )
    (net (code "79") (name "unconnected-(U4-INT1-PadP$11)") (class "Default")
      (node (ref "U4") (pin "P$11") (pinfunction "INT1_P$11") (pintype "bidirectional"))
    )
    (net (code "80") (name "unconnected-(U4-INT2-PadP$9)") (class "Default")
      (node (ref "U4") (pin "P$9") (pinfunction "INT2_P$9") (pintype "bidirectional"))
    )
    (net (code "81") (name "unconnected-(U4-NC-PadP$2)") (class "Default")
      (node (ref "U4") (pin "P$2") (pinfunction "NC_P$2") (pintype "bidirectional"))
    )
    (net (code "82") (name "unconnected-(U4-NC-PadP$3)") (class "Default")
      (node (ref "U4") (pin "P$3") (pinfunction "NC_P$3") (pintype "bidirectional"))
    )
    (net (code "83") (name "unconnected-(U4-SDO-PadP$7)") (class "Default")
      (node (ref "U4") (pin "P$7") (pinfunction "SDO_P$7") (pintype "bidirectional"))
    )
    (net (code "84") (name "unconnected-(U5-NC-PadP$3)") (class "Default")
      (node (ref "U5") (pin "P$3") (pinfunction "NC_P$3") (pintype "bidirectional"))
    )
    (net (code "85") (name "unconnected-(U5-NC-PadP$5)") (class "Default")
      (node (ref "U5") (pin "P$5") (pinfunction "NC_P$5") (pintype "bidirectional"))
    )
    (net (code "86") (name "unconnected-(U5-NC-PadP$6)") (class "Default")
      (node (ref "U5") (pin "P$6") (pinfunction "NC_P$6") (pintype "bidirectional"))
    )
    (net (code "87") (name "unconnected-(U5-NC-PadP$7)") (class "Default")
      (node (ref "U5") (pin "P$7") (pinfunction "NC_P$7") (pintype "bidirectional"))
    )
    (net (code "88") (name "unconnected-(U5-NC-PadP$14)") (class "Default")
      (node (ref "U5") (pin "P$14") (pinfunction "NC_P$14") (pintype "bidirectional"))
    )
    (net (code "89") (name "unconnected-(U6-NC-PadP$10)") (class "Default")
      (node (ref "U6") (pin "P$10") (pinfunction "NC_P$10") (pintype "bidirectional"))
    )
    (net (code "90") (name "unconnected-(U6-RES-PadP$3)") (class "Default")
      (node (ref "U6") (pin "P$3") (pinfunction "RES_P$3") (pintype "bidirectional"))
    )
    (net (code "91") (name "unconnected-(U6-RES-PadP$11)") (class "Default")
      (node (ref "U6") (pin "P$11") (pinfunction "RES_P$11") (pintype "bidirectional"))
    )
    (net (code "92") (name "unconnected-(U6-SDO-PadP$12)") (class "Default")
      (node (ref "U6") (pin "P$12") (pinfunction "SDO_P$12") (pintype "bidirectional"))
    )
  )
)
